# wall-ink.net
KiCad netlist of a schematic drawn in EAGLE
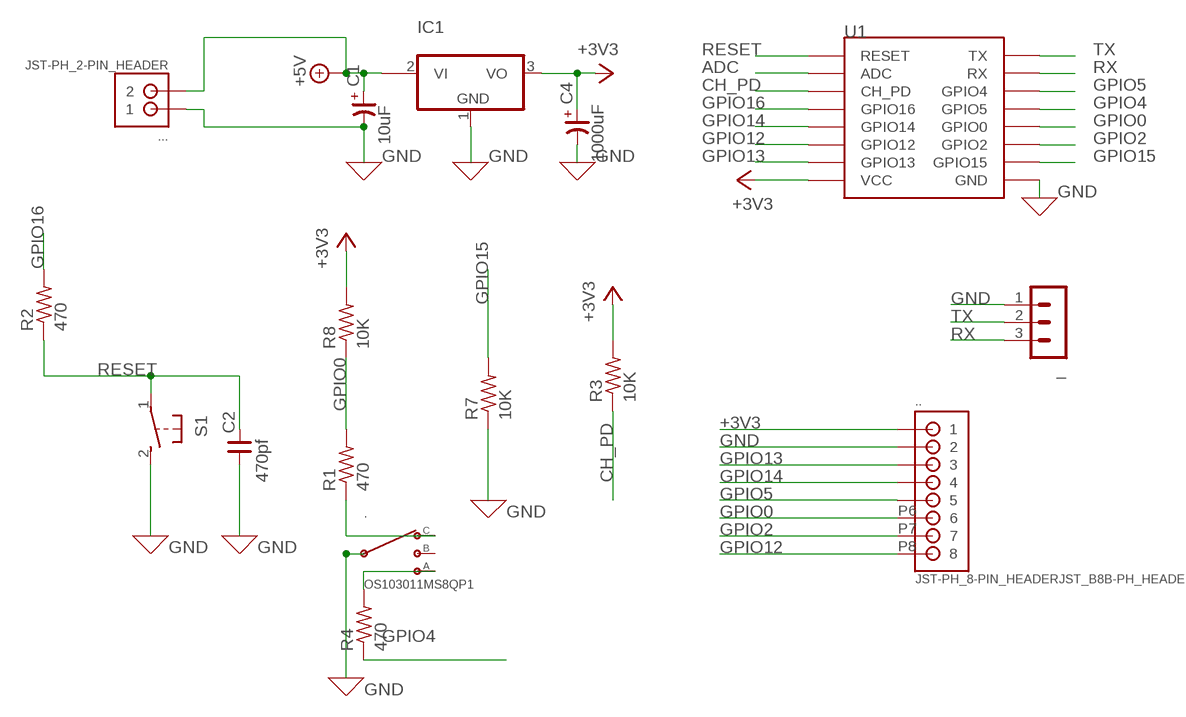
[diagram p0: schematic, sheet 1]

(export (version "E")
  (design (tool "Eeschema 10.0.6"))
  (components
    (comp (ref ".")
      (value "OS103011MS8QP1")
      (footprint "eagle-import:OS102011MS8QP1")
      (libsource (lib "eagle-import") (part "OS103011MS8QP1"))
    )
    (comp (ref "..")
      (value "JST-PH_8-PIN_HEADERJST_B8B-PH_HEADER")
      (footprint "eagle-import:JST_B5B-PH_HEADER")
      (libsource (lib "eagle-import") (part "JST-PH_8-PIN_HEADERJST_B8B-PH_HEADER"))
    )
    (comp (ref "...")
      (value "JST-PH_2-PIN_HEADER")
      (footprint "eagle-import:JST_B2B-PH_HEADER")
      (libsource (lib "eagle-import") (part "JST-PH_2-PIN_HEADER"))
    )
    (comp (ref "C1")
      (value "10uF")
      (footprint "eagle-import:E-020X050")
      (libsource (lib "eagle-import") (part "CP-E-020X050"))
    )
    (comp (ref "C2")
      (value "470pf")
      (footprint "eagle-import:C025-040X018")
      (libsource (lib "eagle-import") (part "CNP-C025-040X018"))
    )
    (comp (ref "C4")
      (value "1000uF")
      (footprint "eagle-import:E-050X100")
      (libsource (lib "eagle-import") (part "CP-E-050X100"))
    )
    (comp (ref "IC1")
      (value "MCP170312MB")
      (footprint "eagle-import:SOT89")
      (libsource (lib "eagle-import") (part "MCP1703MB12"))
    )
    (comp (ref "R1")
      (value "470")
      (footprint "eagle-import:0204_5")
      (libsource (lib "eagle-import") (part "R-US_0204/5"))
    )
    (comp (ref "R2")
      (value "470")
      (footprint "eagle-import:0204_5")
      (libsource (lib "eagle-import") (part "R-US_0204/5"))
    )
    (comp (ref "R3")
      (value "10K")
      (footprint "eagle-import:0204_5")
      (libsource (lib "eagle-import") (part "R-US_0204/5"))
    )
    (comp (ref "R4")
      (value "470")
      (footprint "eagle-import:0204_5")
      (libsource (lib "eagle-import") (part "R-US_0204/5"))
    )
    (comp (ref "R7")
      (value "10K")
      (footprint "eagle-import:0204_5")
      (libsource (lib "eagle-import") (part "R-US_0204/5"))
    )
    (comp (ref "R8")
      (value "10K")
      (footprint "eagle-import:0204_5")
      (libsource (lib "eagle-import") (part "R-US_0204/5"))
    )
    (comp (ref "S1")
      (value "31-XX")
      (footprint "eagle-import:B3F-31XX")
      (fields (field (name "MPN") "B3F-3100"))
      (libsource (lib "eagle-import") (part "31-XX"))
    )
    (comp (ref "U1")
      (value "ESP12SMD")
      (footprint "eagle-import:ESP12-SMD")
      (libsource (lib "eagle-import") (part "ESP12SMD"))
    )
    (comp (ref "_")
      (value "MA03-1")
      (footprint "eagle-import:MA03-1")
      (libsource (lib "eagle-import") (part "MA03-1"))
    )
  )
  (nets
    (net (code "1") (name "+3V3") (class "Default")
      (node (ref "..") (pin "P1") (pinfunction "1_P1") (pintype "bidirectional"))
      (node (ref "C4") (pin "+") (pinfunction "+_+") (pintype "passive"))
      (node (ref "IC1") (pin "3") (pinfunction "VO_3") (pintype "passive"))
      (node (ref "R3") (pin "2") (pinfunction "2_2") (pintype "passive"))
      (node (ref "R8") (pin "2") (pinfunction "2_2") (pintype "passive"))
      (node (ref "U1") (pin "VCC") (pinfunction "VCC_VCC") (pintype "bidirectional"))
    )
    (net (code "2") (name "+5V") (class "Default")
      (node (ref "...") (pin "P2") (pinfunction "2_P2") (pintype "bidirectional"))
      (node (ref "C1") (pin "+") (pinfunction "+_+") (pintype "passive"))
      (node (ref "IC1") (pin "2@1") (pinfunction "VI1_2@1") (pintype "input"))
    )
    (net (code "3") (name "/ADC") (class "Default")
      (node (ref "U1") (pin "ADC") (pinfunction "ADC_ADC") (pintype "bidirectional"))
    )
    (net (code "4") (name "/CH_PD") (class "Default")
      (node (ref "R3") (pin "1") (pinfunction "1_1") (pintype "passive"))
      (node (ref "U1") (pin "CH_PD") (pinfunction "CH_PD_CH_PD") (pintype "bidirectional"))
    )
    (net (code "5") (name "/GPIO0") (class "Default")
      (node (ref "..") (pin "P6") (pinfunction "6_P6") (pintype "bidirectional"))
      (node (ref "R1") (pin "2") (pinfunction "2_2") (pintype "passive"))
      (node (ref "R8") (pin "1") (pinfunction "1_1") (pintype "passive"))
      (node (ref "U1") (pin "GPIO0") (pinfunction "GPIO0_GPIO0") (pintype "bidirectional"))
    )
    (net (code "6") (name "/GPIO2") (class "Default")
      (node (ref "..") (pin "P7") (pinfunction "7_P7") (pintype "bidirectional"))
      (node (ref "U1") (pin "GPIO2") (pinfunction "GPIO2_GPIO2") (pintype "bidirectional"))
    )
    (net (code "7") (name "/GPIO4") (class "Default")
      (node (ref "R4") (pin "1") (pinfunction "1_1") (pintype "passive"))
      (node (ref "U1") (pin "GPIO5") (pinfunction "GPIO5_GPIO5") (pintype "bidirectional"))
    )
    (net (code "8") (name "/GPIO5") (class "Default")
      (node (ref "..") (pin "P5") (pinfunction "5_P5") (pintype "bidirectional"))
      (node (ref "U1") (pin "GPIO4") (pinfunction "GPIO4_GPIO4") (pintype "bidirectional"))
    )
    (net (code "9") (name "/GPIO12") (class "Default")
      (node (ref "..") (pin "P8") (pinfunction "8_P8") (pintype "bidirectional"))
      (node (ref "U1") (pin "GPIO12") (pinfunction "GPIO12_GPIO12") (pintype "bidirectional"))
    )
    (net (code "10") (name "/GPIO13") (class "Default")
      (node (ref "..") (pin "P3") (pinfunction "3_P3") (pintype "bidirectional"))
      (node (ref "U1") (pin "GPIO13") (pinfunction "GPIO13_GPIO13") (pintype "bidirectional"))
    )
    (net (code "11") (name "/GPIO14") (class "Default")
      (node (ref "..") (pin "P4") (pinfunction "4_P4") (pintype "bidirectional"))
      (node (ref "U1") (pin "GPIO14") (pinfunction "GPIO14_GPIO14") (pintype "bidirectional"))
    )
    (net (code "12") (name "/GPIO15") (class "Default")
      (node (ref "R7") (pin "2") (pinfunction "2_2") (pintype "passive"))
      (node (ref "U1") (pin "GPIO15") (pinfunction "GPIO15_GPIO15") (pintype "bidirectional"))
    )
    (net (code "13") (name "/GPIO16") (class "Default")
      (node (ref "R2") (pin "2") (pinfunction "2_2") (pintype "passive"))
      (node (ref "U1") (pin "GPIO16") (pinfunction "GPIO16_GPIO16") (pintype "bidirectional"))
    )
    (net (code "14") (name "/RESET") (class "Default")
      (node (ref "C2") (pin "2") (pinfunction "2_2") (pintype "passive"))
      (node (ref "R2") (pin "1") (pinfunction "1_1") (pintype "passive"))
      (node (ref "S1") (pin "1") (pinfunction "P_1") (pintype "passive"))
      (node (ref "U1") (pin "RESET") (pinfunction "RESET_RESET") (pintype "bidirectional"))
    )
    (net (code "15") (name "/RX") (class "Default")
      (node (ref "U1") (pin "RXD0") (pinfunction "RX_RXD0") (pintype "bidirectional"))
      (node (ref "_") (pin "3") (pinfunction "3_3") (pintype "passive"))
    )
    (net (code "16") (name "/TX") (class "Default")
      (node (ref "U1") (pin "TXD0") (pinfunction "TX_TXD0") (pintype "bidirectional"))
      (node (ref "_") (pin "2") (pinfunction "2_2") (pintype "passive"))
    )
    (net (code "17") (name "GND") (class "Default")
      (node (ref ".") (pin "2") (pinfunction "C_2") (pintype "bidirectional"))
      (node (ref "..") (pin "P2") (pinfunction "2_P2") (pintype "bidirectional"))
      (node (ref "...") (pin "P1") (pinfunction "1_P1") (pintype "bidirectional"))
      (node (ref "C1") (pin "-") (pinfunction "-_-") (pintype "passive"))
      (node (ref "C2") (pin "1") (pinfunction "1_1") (pintype "passive"))
      (node (ref "C4") (pin "-") (pinfunction "-_-") (pintype "passive"))
      (node (ref "IC1") (pin "1") (pinfunction "GND_1") (pintype "passive"))
      (node (ref "R7") (pin "1") (pinfunction "1_1") (pintype "passive"))
      (node (ref "S1") (pin "2") (pinfunction "S_2") (pintype "passive"))
      (node (ref "U1") (pin "GND") (pinfunction "GND_GND") (pintype "bidirectional"))
      (node (ref "_") (pin "1") (pinfunction "1_1") (pintype "passive"))
    )
    (net (code "18") (name "Net-(.-3)") (class "Default")
      (node (ref ".") (pin "4") (pinfunction "3_4") (pintype "bidirectional"))
      (node (ref "R1") (pin "1") (pinfunction "1_1") (pintype "passive"))
    )
    (net (code "19") (name "Net-(.-Pad1)") (class "Default")
      (node (ref ".") (pin "1") (pinfunction "1_1") (pintype "bidirectional"))
      (node (ref "R4") (pin "2") (pinfunction "2_2") (pintype "passive"))
    )
    (net (code "20") (name "unconnected-(.-2-Pad3)") (class "Default")
      (node (ref ".") (pin "3") (pinfunction "2_3") (pintype "bidirectional"))
    )
    (net (code "21") (name "unconnected-(IC1-VI-Pad2)") (class "Default")
      (node (ref "IC1") (pin "2") (pinfunction "VI_2") (pintype "input"))
    )
  )
)
